# usb.net
KiCad netlist of a schematic drawn in EAGLE
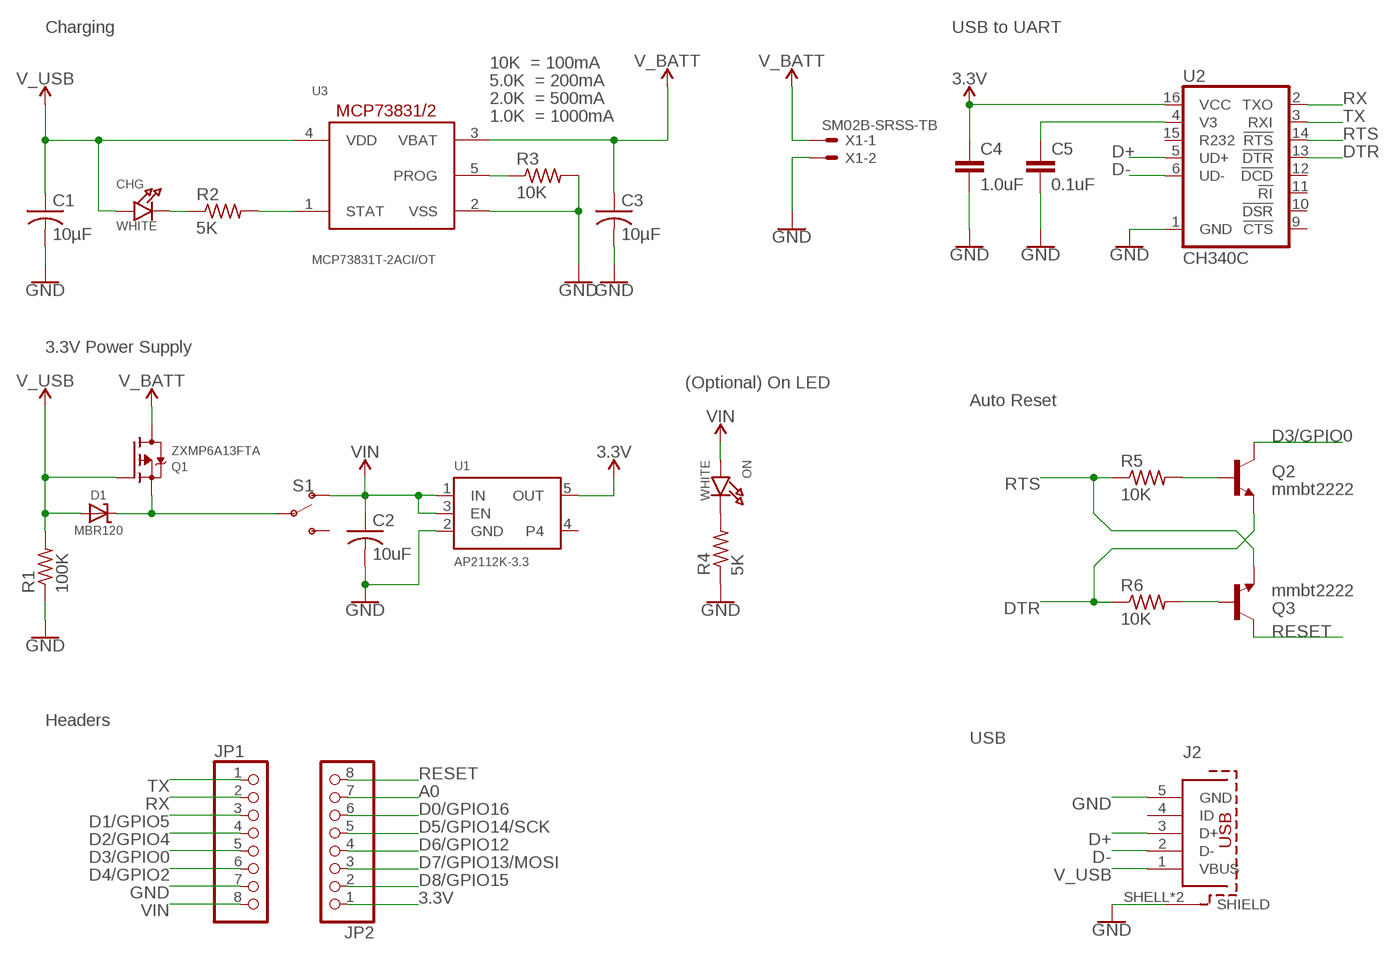
[diagram p0: schematic, sheet 1]

(export (version "E")
  (design (tool "Eeschema 10.0.6"))
  (components
    (comp (ref "C1")
      (value "10µF")
      (footprint "eagle-import:C0805")
      (fields (field (name "MPN") "CL21A106KPFNNNE"))
      (libsource (lib "eagle-import") (part "C-USC0805"))
    )
    (comp (ref "C2")
      (value "10uF")
      (footprint "eagle-import:C0805")
      (fields (field (name "MPN") "CL21A106KPFNNNE"))
      (libsource (lib "eagle-import") (part "C-USC0805"))
    )
    (comp (ref "C3")
      (value "10µF")
      (footprint "eagle-import:C0805")
      (fields (field (name "MPN") "CL21A106KPFNNNE"))
      (libsource (lib "eagle-import") (part "C-USC0805"))
    )
    (comp (ref "C4")
      (value "1.0uF")
      (footprint "eagle-import:0805")
      (fields (field (name "MPN") "C0805C105K4RAC7210"))
      (libsource (lib "eagle-import") (part "1.0UF-0805-25V-10%"))
    )
    (comp (ref "C5")
      (value "0.1uF")
      (footprint "eagle-import:0805")
      (fields (field (name "MPN") "C0805C104M3RACTU"))
      (libsource (lib "eagle-import") (part "1.0UF-0805-25V-10%"))
    )
    (comp (ref "CHG")
      (value "WHITE")
      (footprint "eagle-import:CHIPLED_0805_NOOUTLINE")
      (fields (field (name "MPN") "NCD0805W2"))
      (libsource (lib "eagle-import") (part "LED0805_NOOUTLINE"))
    )
    (comp (ref "D1")
      (value "MBR120")
      (footprint "eagle-import:SOD-123")
      (fields (field (name "MPN") "MBR120ESFT1G"))
      (libsource (lib "eagle-import") (part "DIODE-SCHOTTKYSOD-123"))
    )
    (comp (ref "J2")
      (value "614105150621")
      (footprint "eagle-import:614105150621")
      (fields (field (name "MPN") "U-D-M5DD-W-1"))
      (libsource (lib "eagle-import") (part "614105150621"))
    )
    (comp (ref "JP1")
      (value "PINHD-1X8CLEANBIG")
      (footprint "eagle-import:1X08-CLEANBIG")
      (fields (field (name "MPN") "C27438"))
      (libsource (lib "eagle-import") (part "PINHD-1X8CLEANBIG"))
    )
    (comp (ref "JP2")
      (value "PINHD-1X8CLEANBIG")
      (footprint "eagle-import:1X08-CLEANBIG")
      (fields (field (name "MPN") "C27438"))
      (libsource (lib "eagle-import") (part "PINHD-1X8CLEANBIG"))
    )
    (comp (ref "ON")
      (value "WHITE")
      (footprint "eagle-import:CHIPLED_0805_NOOUTLINE")
      (fields (field (name "MPN") "NCD0805W2"))
      (libsource (lib "eagle-import") (part "LED0805_NOOUTLINE"))
    )
    (comp (ref "Q1")
      (value "ZXMP6A13FTA")
      (footprint "eagle-import:SOT23-R")
      (libsource (lib "eagle-import") (part "MOSFET-P"))
    )
    (comp (ref "Q2")
      (value "mmbt2222")
      (footprint "eagle-import:SOT23-3")
      (fields (field (name "MPN") "MMBT2222A-G"))
      (libsource (lib "eagle-import") (part "TRANSISTOR_NPNSOT23-3"))
    )
    (comp (ref "Q3")
      (value "mmbt2222")
      (footprint "eagle-import:SOT23-3")
      (fields (field (name "MPN") "MMBT2222A-G"))
      (libsource (lib "eagle-import") (part "TRANSISTOR_NPNSOT23-3"))
    )
    (comp (ref "R1")
      (value "100K")
      (footprint "eagle-import:R0805")
      (fields (field (name "MPN") "0805W8F1003T5E"))
      (libsource (lib "eagle-import") (part "R-US_R0805"))
    )
    (comp (ref "R2")
      (value "5K")
      (footprint "eagle-import:R0805")
      (fields (field (name "MPN") "0805W8F4871T5E"))
      (libsource (lib "eagle-import") (part "R-US_R0805"))
    )
    (comp (ref "R3")
      (value "10K")
      (footprint "eagle-import:R0805")
      (fields (field (name "MPN") "CRCW080510K0FKEAC"))
      (libsource (lib "eagle-import") (part "R-US_R0805"))
    )
    (comp (ref "R4")
      (value "5K")
      (footprint "eagle-import:R0805")
      (fields (field (name "MPN") "0805W8F4871T5E"))
      (libsource (lib "eagle-import") (part "R-US_R0805"))
    )
    (comp (ref "R5")
      (value "10K")
      (footprint "eagle-import:R0603")
      (fields (field (name "MPN") "RC0603FR-0710KL"))
      (libsource (lib "eagle-import") (part "R-US_R0603"))
    )
    (comp (ref "R6")
      (value "10K")
      (footprint "eagle-import:R0603")
      (fields (field (name "MPN") "RC0603FR-0710KL"))
      (libsource (lib "eagle-import") (part "R-US_R0603"))
    )
    (comp (ref "S1")
      (value "SWITCH-SPDT-SMD-AYZ0202")
      (footprint "eagle-import:SWITCH_DPDT_SMD_AYZ0202")
      (fields (field (name "MPN") "AYZ0202AGRLC"))
      (libsource (lib "eagle-import") (part "SWITCH-SPDT-SMD-AYZ0202"))
    )
    (comp (ref "U1")
      (value "AP2112K-3.3")
      (footprint "eagle-import:SOT23-5")
      (libsource (lib "eagle-import") (part "VREG_SOT23-5"))
    )
    (comp (ref "U2")
      (value "CH340C")
      (footprint "eagle-import:SO016")
      (libsource (lib "eagle-import") (part "CH340C"))
    )
    (comp (ref "U3")
      (value "MCP73831T-2ACI/OT")
      (footprint "eagle-import:SOT23-5L")
      (libsource (lib "eagle-import") (part "MCP73831/OT"))
    )
    (comp (ref "X1")
      (value "SM02B-SRSS-TB")
      (footprint "eagle-import:SM02B-SRSS-TB")
      (fields (field (name "MPN") "SM02B-SRSS-TB"))
      (libsource (lib "eagle-import") (part "?M02B-SRSS-TBS"))
    )
  )
  (nets
    (net (code "1") (name "/A0") (class "Default")
      (node (ref "JP2") (pin "7") (pinfunction "7_7") (pintype "passive"))
    )
    (net (code "2") (name "/D+") (class "Default")
      (node (ref "J2") (pin "3") (pinfunction "D+_3") (pintype "passive"))
      (node (ref "U2") (pin "5") (pinfunction "UD+_5") (pintype "bidirectional"))
    )
    (net (code "3") (name "/D-") (class "Default")
      (node (ref "J2") (pin "2") (pinfunction "D-_2") (pintype "passive"))
      (node (ref "U2") (pin "6") (pinfunction "UD-_6") (pintype "bidirectional"))
    )
    (net (code "4") (name "/D0{slash}GPIO16") (class "Default")
      (node (ref "JP2") (pin "6") (pinfunction "6_6") (pintype "passive"))
    )
    (net (code "5") (name "/D1{slash}GPIO5") (class "Default")
      (node (ref "JP1") (pin "3") (pinfunction "3_3") (pintype "passive"))
    )
    (net (code "6") (name "/D2{slash}GPIO4") (class "Default")
      (node (ref "JP1") (pin "4") (pinfunction "4_4") (pintype "passive"))
    )
    (net (code "7") (name "/D3{slash}GPIO0") (class "Default")
      (node (ref "JP1") (pin "5") (pinfunction "5_5") (pintype "passive"))
      (node (ref "Q2") (pin "3") (pinfunction "C_3") (pintype "passive"))
    )
    (net (code "8") (name "/D4{slash}GPIO2") (class "Default")
      (node (ref "JP1") (pin "6") (pinfunction "6_6") (pintype "passive"))
    )
    (net (code "9") (name "/D5{slash}GPIO14{slash}SCK") (class "Default")
      (node (ref "JP2") (pin "5") (pinfunction "5_5") (pintype "passive"))
    )
    (net (code "10") (name "/D6{slash}GPIO12") (class "Default")
      (node (ref "JP2") (pin "4") (pinfunction "4_4") (pintype "passive"))
    )
    (net (code "11") (name "/D7{slash}GPIO13{slash}MOSI") (class "Default")
      (node (ref "JP2") (pin "3") (pinfunction "3_3") (pintype "passive"))
    )
    (net (code "12") (name "/D8{slash}GPIO15") (class "Default")
      (node (ref "JP2") (pin "2") (pinfunction "2_2") (pintype "passive"))
    )
    (net (code "13") (name "/DTR") (class "Default")
      (node (ref "Q2") (pin "2") (pinfunction "E_2") (pintype "passive"))
      (node (ref "R6") (pin "1") (pinfunction "1_1") (pintype "passive"))
      (node (ref "U2") (pin "13") (pinfunction "~{DTR}_13") (pintype "bidirectional"))
    )
    (net (code "14") (name "/RESET") (class "Default")
      (node (ref "JP2") (pin "8") (pinfunction "8_8") (pintype "passive"))
      (node (ref "Q3") (pin "3") (pinfunction "C_3") (pintype "passive"))
    )
    (net (code "15") (name "/RTS") (class "Default")
      (node (ref "Q3") (pin "2") (pinfunction "E_2") (pintype "passive"))
      (node (ref "R5") (pin "1") (pinfunction "1_1") (pintype "passive"))
      (node (ref "U2") (pin "14") (pinfunction "~{RTS}_14") (pintype "bidirectional"))
    )
    (net (code "16") (name "/RX") (class "Default")
      (node (ref "JP1") (pin "2") (pinfunction "2_2") (pintype "passive"))
      (node (ref "U2") (pin "2") (pinfunction "TXO_2") (pintype "bidirectional"))
    )
    (net (code "17") (name "/TX") (class "Default")
      (node (ref "JP1") (pin "1") (pinfunction "1_1") (pintype "passive"))
      (node (ref "U2") (pin "3") (pinfunction "RXI_3") (pintype "bidirectional"))
    )
    (net (code "18") (name "3.3V") (class "Default")
      (node (ref "C4") (pin "1") (pinfunction "1_1") (pintype "passive"))
      (node (ref "JP2") (pin "1") (pinfunction "1_1") (pintype "passive"))
      (node (ref "U1") (pin "5") (pinfunction "OUT_5") (pintype "power_in"))
      (node (ref "U2") (pin "16") (pinfunction "VCC_16") (pintype "bidirectional"))
    )
    (net (code "19") (name "GND") (class "Default")
      (node (ref "C1") (pin "2") (pinfunction "2_2") (pintype "passive"))
      (node (ref "C2") (pin "2") (pinfunction "2_2") (pintype "passive"))
      (node (ref "C3") (pin "2") (pinfunction "2_2") (pintype "passive"))
      (node (ref "C4") (pin "2") (pinfunction "2_2") (pintype "passive"))
      (node (ref "C5") (pin "2") (pinfunction "2_2") (pintype "passive"))
      (node (ref "J2") (pin "5") (pinfunction "GND_5") (pintype "passive"))
      (node (ref "J2") (pin "SHELL") (pinfunction "SHIELD_SHELL") (pintype "passive"))
      (node (ref "J2") (pin "SHELL1") (pinfunction "SHIELD_SHELL1") (pintype "passive"))
      (node (ref "JP1") (pin "7") (pinfunction "7_7") (pintype "passive"))
      (node (ref "R1") (pin "1") (pinfunction "1_1") (pintype "passive"))
      (node (ref "R3") (pin "2") (pinfunction "2_2") (pintype "passive"))
      (node (ref "R4") (pin "1") (pinfunction "1_1") (pintype "passive"))
      (node (ref "U1") (pin "2") (pinfunction "GND_2") (pintype "power_in"))
      (node (ref "U2") (pin "1") (pinfunction "GND_1") (pintype "bidirectional"))
      (node (ref "U3") (pin "2") (pinfunction "VSS_2") (pintype "power_in"))
      (node (ref "X1") (pin "2") (pinfunction "S_2") (pintype "passive"))
    )
    (net (code "20") (name "Net-(CHG-PadC)") (class "Default")
      (node (ref "CHG") (pin "C") (pinfunction "C_C") (pintype "passive"))
      (node (ref "R2") (pin "1") (pinfunction "1_1") (pintype "passive"))
    )
    (net (code "21") (name "Net-(ON-PadC)") (class "Default")
      (node (ref "ON") (pin "C") (pinfunction "C_C") (pintype "passive"))
      (node (ref "R4") (pin "2") (pinfunction "2_2") (pintype "passive"))
    )
    (net (code "22") (name "Net-(Q1-S)") (class "Default")
      (node (ref "D1") (pin "C") (pinfunction "C_C") (pintype "passive"))
      (node (ref "Q1") (pin "2") (pinfunction "S_2") (pintype "passive"))
      (node (ref "S1") (pin "5") (pinfunction "P_5") (pintype "passive"))
    )
    (net (code "23") (name "Net-(Q2-B)") (class "Default")
      (node (ref "Q2") (pin "1") (pinfunction "B_1") (pintype "passive"))
      (node (ref "R5") (pin "2") (pinfunction "2_2") (pintype "passive"))
    )
    (net (code "24") (name "Net-(Q3-B)") (class "Default")
      (node (ref "Q3") (pin "1") (pinfunction "B_1") (pintype "passive"))
      (node (ref "R6") (pin "2") (pinfunction "2_2") (pintype "passive"))
    )
    (net (code "25") (name "Net-(U2-V3)") (class "Default")
      (node (ref "C5") (pin "1") (pinfunction "1_1") (pintype "passive"))
      (node (ref "U2") (pin "4") (pinfunction "V3_4") (pintype "bidirectional"))
    )
    (net (code "26") (name "Net-(U3-PROG)") (class "Default")
      (node (ref "R3") (pin "1") (pinfunction "1_1") (pintype "passive"))
      (node (ref "U3") (pin "5") (pinfunction "PROG_5") (pintype "input"))
    )
    (net (code "27") (name "Net-(U3-STAT)") (class "Default")
      (node (ref "R2") (pin "2") (pinfunction "2_2") (pintype "passive"))
      (node (ref "U3") (pin "1") (pinfunction "STAT_1") (pintype "output"))
    )
    (net (code "28") (name "VIN") (class "Default")
      (node (ref "C2") (pin "1") (pinfunction "1_1") (pintype "passive"))
      (node (ref "JP1") (pin "8") (pinfunction "8_8") (pintype "passive"))
      (node (ref "ON") (pin "A") (pinfunction "A_A") (pintype "passive"))
      (node (ref "S1") (pin "6") (pinfunction "O_6") (pintype "passive"))
      (node (ref "U1") (pin "1") (pinfunction "IN_1") (pintype "power_in"))
      (node (ref "U1") (pin "3") (pinfunction "EN_3") (pintype "input"))
    )
    (net (code "29") (name "V_BATT") (class "Default")
      (node (ref "C3") (pin "1") (pinfunction "1_1") (pintype "passive"))
      (node (ref "Q1") (pin "3") (pinfunction "D_3") (pintype "passive"))
      (node (ref "U3") (pin "3") (pinfunction "VBAT_3") (pintype "bidirectional"))
      (node (ref "X1") (pin "1") (pinfunction "S_1") (pintype "passive"))
    )
    (net (code "30") (name "V_USB") (class "Default")
      (node (ref "C1") (pin "1") (pinfunction "1_1") (pintype "passive"))
      (node (ref "CHG") (pin "A") (pinfunction "A_A") (pintype "passive"))
      (node (ref "D1") (pin "A") (pinfunction "A_A") (pintype "passive"))
      (node (ref "J2") (pin "1") (pinfunction "VBUS_1") (pintype "passive"))
      (node (ref "Q1") (pin "1") (pinfunction "G_1") (pintype "passive"))
      (node (ref "R1") (pin "2") (pinfunction "2_2") (pintype "passive"))
      (node (ref "U3") (pin "4") (pinfunction "VDD_4") (pintype "power_in"))
    )
    (net (code "31") (name "unconnected-(J2-ID-Pad4)") (class "Default")
      (node (ref "J2") (pin "4") (pinfunction "ID_4") (pintype "passive"))
    )
    (net (code "32") (name "unconnected-(S1-S-Pad4)") (class "Default")
      (node (ref "S1") (pin "4") (pinfunction "S_4") (pintype "passive"))
    )
    (net (code "33") (name "unconnected-(U1-P4-Pad4)") (class "Default")
      (node (ref "U1") (pin "4") (pinfunction "P4_4") (pintype "bidirectional"))
    )
    (net (code "34") (name "unconnected-(U2-R232-Pad15)") (class "Default")
      (node (ref "U2") (pin "15") (pinfunction "R232_15") (pintype "bidirectional"))
    )
    (net (code "35") (name "unconnected-(U2-~{CTS}-Pad9)") (class "Default")
      (node (ref "U2") (pin "9") (pinfunction "~{CTS}_9") (pintype "bidirectional"))
    )
    (net (code "36") (name "unconnected-(U2-~{DCD}-Pad12)") (class "Default")
      (node (ref "U2") (pin "12") (pinfunction "~{DCD}_12") (pintype "bidirectional"))
    )
    (net (code "37") (name "unconnected-(U2-~{DSR}-Pad10)") (class "Default")
      (node (ref "U2") (pin "10") (pinfunction "~{DSR}_10") (pintype "bidirectional"))
    )
    (net (code "38") (name "unconnected-(U2-~{RI}-Pad11)") (class "Default")
      (node (ref "U2") (pin "11") (pinfunction "~{RI}_11") (pintype "bidirectional"))
    )
  )
)
